# TPS62736.net
KiCad netlist of a schematic drawn in EAGLE
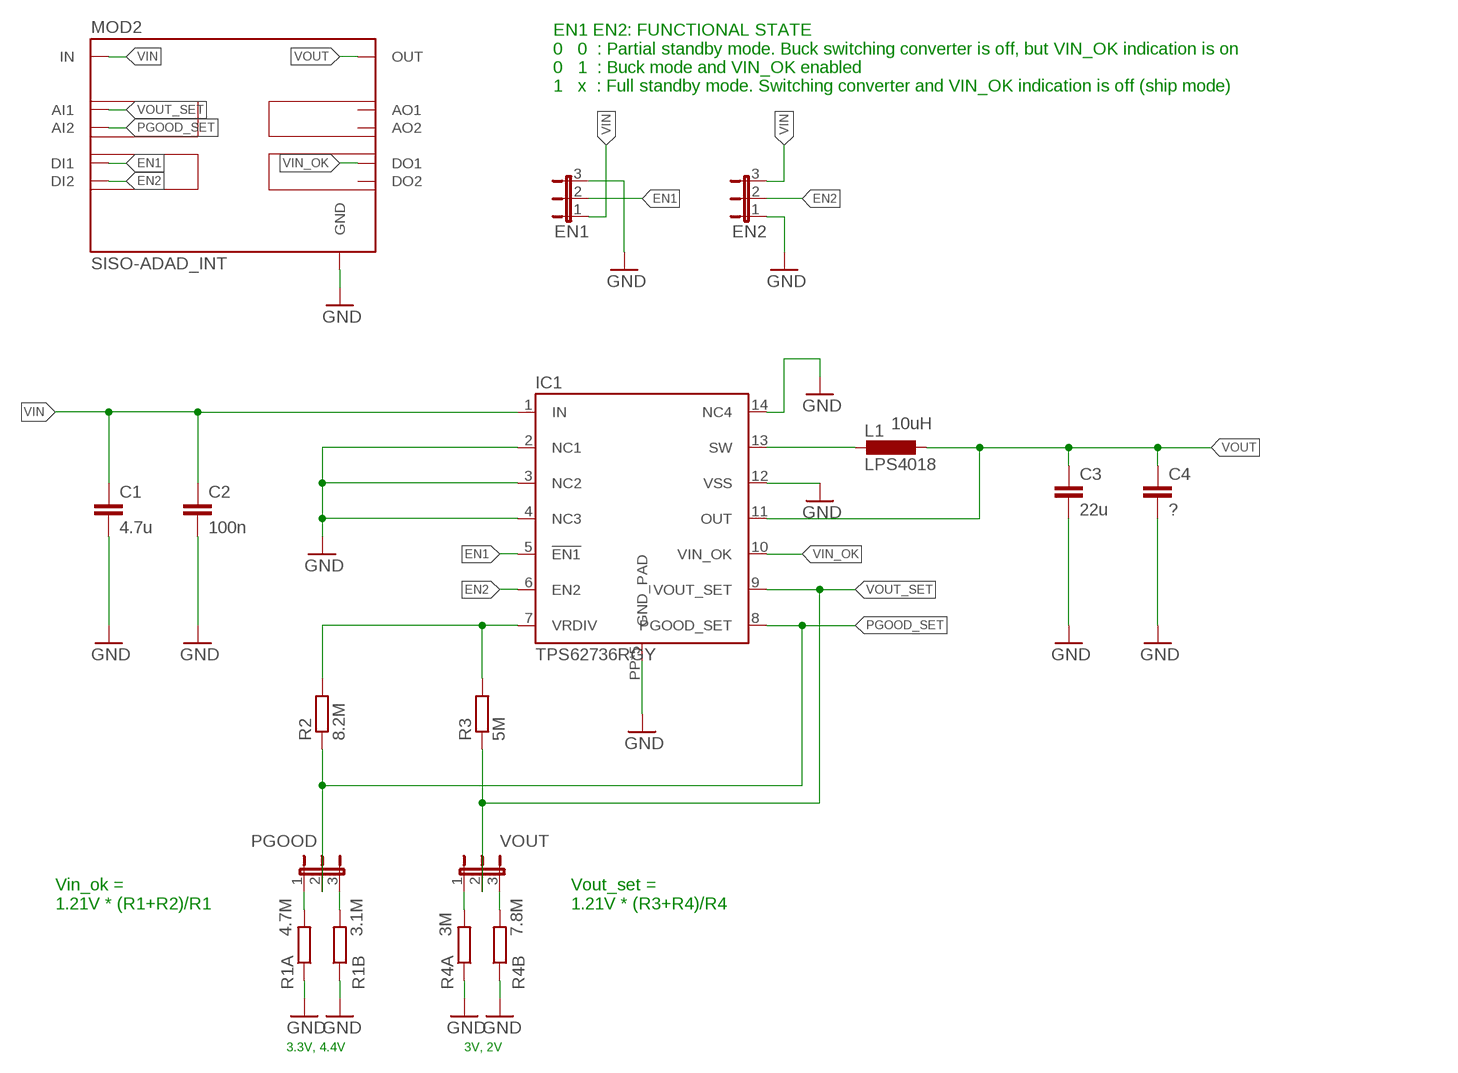
[diagram p0: schematic, sheet 1]

(export (version "E")
  (design (tool "Eeschema 10.0.6"))
  (components
    (comp (ref "C1")
      (value "4.7u")
      (footprint "eagle-import:C0805")
      (libsource (lib "eagle-import") (part "C-EUC0805"))
    )
    (comp (ref "C2")
      (value "100n")
      (footprint "eagle-import:C0805")
      (libsource (lib "eagle-import") (part "C-EUC0805"))
    )
    (comp (ref "C3")
      (value "22u")
      (footprint "eagle-import:C0805")
      (libsource (lib "eagle-import") (part "C-EUC0805"))
    )
    (comp (ref "C4")
      (value "?")
      (footprint "eagle-import:C0805")
      (libsource (lib "eagle-import") (part "C-EUC0805"))
    )
    (comp (ref "EN1")
      (value "JP2E")
      (footprint "eagle-import:JP2")
      (libsource (lib "eagle-import") (part "JP2E"))
    )
    (comp (ref "EN2")
      (value "JP2E")
      (footprint "eagle-import:JP2")
      (libsource (lib "eagle-import") (part "JP2E"))
    )
    (comp (ref "IC1")
      (value "TPS62736RGY")
      (footprint "eagle-import:S-PVQFN-N14")
      (libsource (lib "eagle-import") (part "TPS62736RGY"))
    )
    (comp (ref "L1")
      (value "LPS4018")
      (footprint "eagle-import:LPS4018")
      (libsource (lib "eagle-import") (part "LPS4018"))
    )
    (comp (ref "MOD2")
      (value "SISO-ADAD_INT")
      (footprint "eagle-import:SISO-ADAD")
      (libsource (lib "eagle-import") (part "SISO-ADAD_INT"))
    )
    (comp (ref "PGOOD")
      (value "JP2E")
      (footprint "eagle-import:JP2")
      (libsource (lib "eagle-import") (part "JP2E"))
    )
    (comp (ref "R1A")
      (value "4.7M")
      (footprint "eagle-import:R0805")
      (libsource (lib "eagle-import") (part "R-EU_R0805"))
    )
    (comp (ref "R1B")
      (value "3.1M")
      (footprint "eagle-import:R0805")
      (libsource (lib "eagle-import") (part "R-EU_R0805"))
    )
    (comp (ref "R2")
      (value "8.2M")
      (footprint "eagle-import:R0805")
      (libsource (lib "eagle-import") (part "R-EU_R0805"))
    )
    (comp (ref "R3")
      (value "5M")
      (footprint "eagle-import:R0805")
      (libsource (lib "eagle-import") (part "R-EU_R0805"))
    )
    (comp (ref "R4A")
      (value "3M")
      (footprint "eagle-import:R0805")
      (libsource (lib "eagle-import") (part "R-EU_R0805"))
    )
    (comp (ref "R4B")
      (value "7.8M")
      (footprint "eagle-import:R0805")
      (libsource (lib "eagle-import") (part "R-EU_R0805"))
    )
    (comp (ref "VOUT")
      (value "JP2E")
      (footprint "eagle-import:JP2")
      (libsource (lib "eagle-import") (part "JP2E"))
    )
  )
  (nets
    (net (code "1") (name "EN1") (class "Default")
      (node (ref "EN1") (pin "2") (pinfunction "2_2") (pintype "passive"))
      (node (ref "IC1") (pin "5") (pinfunction "~{EN1}_5") (pintype "bidirectional"))
      (node (ref "MOD2") (pin "DI1") (pinfunction "DI1_DI1") (pintype "output"))
    )
    (net (code "2") (name "EN2") (class "Default")
      (node (ref "EN2") (pin "2") (pinfunction "2_2") (pintype "passive"))
      (node (ref "IC1") (pin "6") (pinfunction "EN2_6") (pintype "bidirectional"))
      (node (ref "MOD2") (pin "DI2") (pinfunction "DI2_DI2") (pintype "output"))
    )
    (net (code "3") (name "GND") (class "Default")
      (node (ref "C1") (pin "2") (pinfunction "2_2") (pintype "passive"))
      (node (ref "C2") (pin "2") (pinfunction "2_2") (pintype "passive"))
      (node (ref "C3") (pin "2") (pinfunction "2_2") (pintype "passive"))
      (node (ref "C4") (pin "2") (pinfunction "2_2") (pintype "passive"))
      (node (ref "EN1") (pin "3") (pinfunction "3_3") (pintype "passive"))
      (node (ref "EN2") (pin "1") (pinfunction "1_1") (pintype "passive"))
      (node (ref "IC1") (pin "12") (pinfunction "VSS_12") (pintype "bidirectional"))
      (node (ref "IC1") (pin "14") (pinfunction "NC4_14") (pintype "bidirectional"))
      (node (ref "IC1") (pin "2") (pinfunction "NC1_2") (pintype "bidirectional"))
      (node (ref "IC1") (pin "3") (pinfunction "NC2_3") (pintype "bidirectional"))
      (node (ref "IC1") (pin "4") (pinfunction "NC3_4") (pintype "bidirectional"))
      (node (ref "IC1") (pin "PP") (pinfunction "GND_PAD_PP") (pintype "bidirectional"))
      (node (ref "IC1") (pin "PP@1") (pinfunction "GND_PAD_PP@1") (pintype "bidirectional"))
      (node (ref "IC1") (pin "PP@2") (pinfunction "GND_PAD_PP@2") (pintype "bidirectional"))
      (node (ref "IC1") (pin "PP@3") (pinfunction "GND_PAD_PP@3") (pintype "bidirectional"))
      (node (ref "IC1") (pin "PP@4") (pinfunction "GND_PAD_PP@4") (pintype "bidirectional"))
      (node (ref "MOD2") (pin "GND1") (pinfunction "GND_GND1") (pintype "power_in"))
      (node (ref "MOD2") (pin "GND2") (pinfunction "GND_GND2") (pintype "power_in"))
      (node (ref "MOD2") (pin "GND3") (pinfunction "GND_GND3") (pintype "power_in"))
      (node (ref "MOD2") (pin "GND4") (pinfunction "GND_GND4") (pintype "power_in"))
      (node (ref "R1A") (pin "1") (pinfunction "1_1") (pintype "passive"))
      (node (ref "R1B") (pin "1") (pinfunction "1_1") (pintype "passive"))
      (node (ref "R4A") (pin "1") (pinfunction "1_1") (pintype "passive"))
      (node (ref "R4B") (pin "1") (pinfunction "1_1") (pintype "passive"))
    )
    (net (code "4") (name "Net-(IC1-SW)") (class "Default")
      (node (ref "IC1") (pin "13") (pinfunction "SW_13") (pintype "bidirectional"))
      (node (ref "L1") (pin "1") (pinfunction "1_1") (pintype "passive"))
    )
    (net (code "5") (name "Net-(IC1-VRDIV)") (class "Default")
      (node (ref "IC1") (pin "7") (pinfunction "VRDIV_7") (pintype "bidirectional"))
      (node (ref "R2") (pin "2") (pinfunction "2_2") (pintype "passive"))
      (node (ref "R3") (pin "2") (pinfunction "2_2") (pintype "passive"))
    )
    (net (code "6") (name "Net-(PGOOD-Pad1)") (class "Default")
      (node (ref "PGOOD") (pin "1") (pinfunction "1_1") (pintype "passive"))
      (node (ref "R1A") (pin "2") (pinfunction "2_2") (pintype "passive"))
    )
    (net (code "7") (name "Net-(PGOOD-Pad3)") (class "Default")
      (node (ref "PGOOD") (pin "3") (pinfunction "3_3") (pintype "passive"))
      (node (ref "R1B") (pin "2") (pinfunction "2_2") (pintype "passive"))
    )
    (net (code "8") (name "Net-(R4A-Pad2)") (class "Default")
      (node (ref "R4A") (pin "2") (pinfunction "2_2") (pintype "passive"))
      (node (ref "VOUT") (pin "1") (pinfunction "1_1") (pintype "passive"))
    )
    (net (code "9") (name "Net-(R4B-Pad2)") (class "Default")
      (node (ref "R4B") (pin "2") (pinfunction "2_2") (pintype "passive"))
      (node (ref "VOUT") (pin "3") (pinfunction "3_3") (pintype "passive"))
    )
    (net (code "10") (name "PGOOD_SET") (class "Default")
      (node (ref "IC1") (pin "8") (pinfunction "PGOOD_SET_8") (pintype "bidirectional"))
      (node (ref "MOD2") (pin "AI2") (pinfunction "AI2_AI2") (pintype "output"))
      (node (ref "PGOOD") (pin "2") (pinfunction "2_2") (pintype "passive"))
      (node (ref "R2") (pin "1") (pinfunction "1_1") (pintype "passive"))
    )
    (net (code "11") (name "VIN") (class "Default")
      (node (ref "C1") (pin "1") (pinfunction "1_1") (pintype "passive"))
      (node (ref "C2") (pin "1") (pinfunction "1_1") (pintype "passive"))
      (node (ref "EN1") (pin "1") (pinfunction "1_1") (pintype "passive"))
      (node (ref "EN2") (pin "3") (pinfunction "3_3") (pintype "passive"))
      (node (ref "IC1") (pin "1") (pinfunction "IN_1") (pintype "bidirectional"))
      (node (ref "MOD2") (pin "IN1") (pinfunction "IN_IN1") (pintype "output"))
      (node (ref "MOD2") (pin "IN2") (pinfunction "IN_IN2") (pintype "output"))
      (node (ref "MOD2") (pin "IN3") (pinfunction "IN_IN3") (pintype "output"))
      (node (ref "MOD2") (pin "IN4") (pinfunction "IN_IN4") (pintype "output"))
    )
    (net (code "12") (name "VIN_OK") (class "Default")
      (node (ref "IC1") (pin "10") (pinfunction "VIN_OK_10") (pintype "bidirectional"))
      (node (ref "MOD2") (pin "DO1") (pinfunction "DO1_DO1") (pintype "input"))
    )
    (net (code "13") (name "VOUT") (class "Default")
      (node (ref "C3") (pin "1") (pinfunction "1_1") (pintype "passive"))
      (node (ref "C4") (pin "1") (pinfunction "1_1") (pintype "passive"))
      (node (ref "IC1") (pin "11") (pinfunction "OUT_11") (pintype "bidirectional"))
      (node (ref "L1") (pin "2") (pinfunction "2_2") (pintype "passive"))
      (node (ref "MOD2") (pin "OUT1_1") (pinfunction "OUT_OUT1_1") (pintype "input"))
      (node (ref "MOD2") (pin "OUT1_2") (pinfunction "OUT_OUT1_2") (pintype "input"))
      (node (ref "MOD2") (pin "OUT1_3") (pinfunction "OUT_OUT1_3") (pintype "input"))
      (node (ref "MOD2") (pin "OUT1_4") (pinfunction "OUT_OUT1_4") (pintype "input"))
    )
    (net (code "14") (name "VOUT_SET") (class "Default")
      (node (ref "IC1") (pin "9") (pinfunction "VOUT_SET_9") (pintype "bidirectional"))
      (node (ref "MOD2") (pin "AI1") (pinfunction "AI1_AI1") (pintype "output"))
      (node (ref "R3") (pin "1") (pinfunction "1_1") (pintype "passive"))
      (node (ref "VOUT") (pin "2") (pinfunction "2_2") (pintype "passive"))
    )
    (net (code "15") (name "unconnected-(MOD2-PadAO1)") (class "Default")
      (node (ref "MOD2") (pin "AO1") (pinfunction "AO1_AO1") (pintype "input"))
    )
    (net (code "16") (name "unconnected-(MOD2-PadAO2)") (class "Default")
      (node (ref "MOD2") (pin "AO2") (pinfunction "AO2_AO2") (pintype "input"))
    )
    (net (code "17") (name "unconnected-(MOD2-PadDO2)") (class "Default")
      (node (ref "MOD2") (pin "DO2") (pinfunction "DO2_DO2") (pintype "input"))
    )
  )
)
